# Kube_LoRaWAN_Module.net
KiCad netlist of a schematic drawn in EAGLE
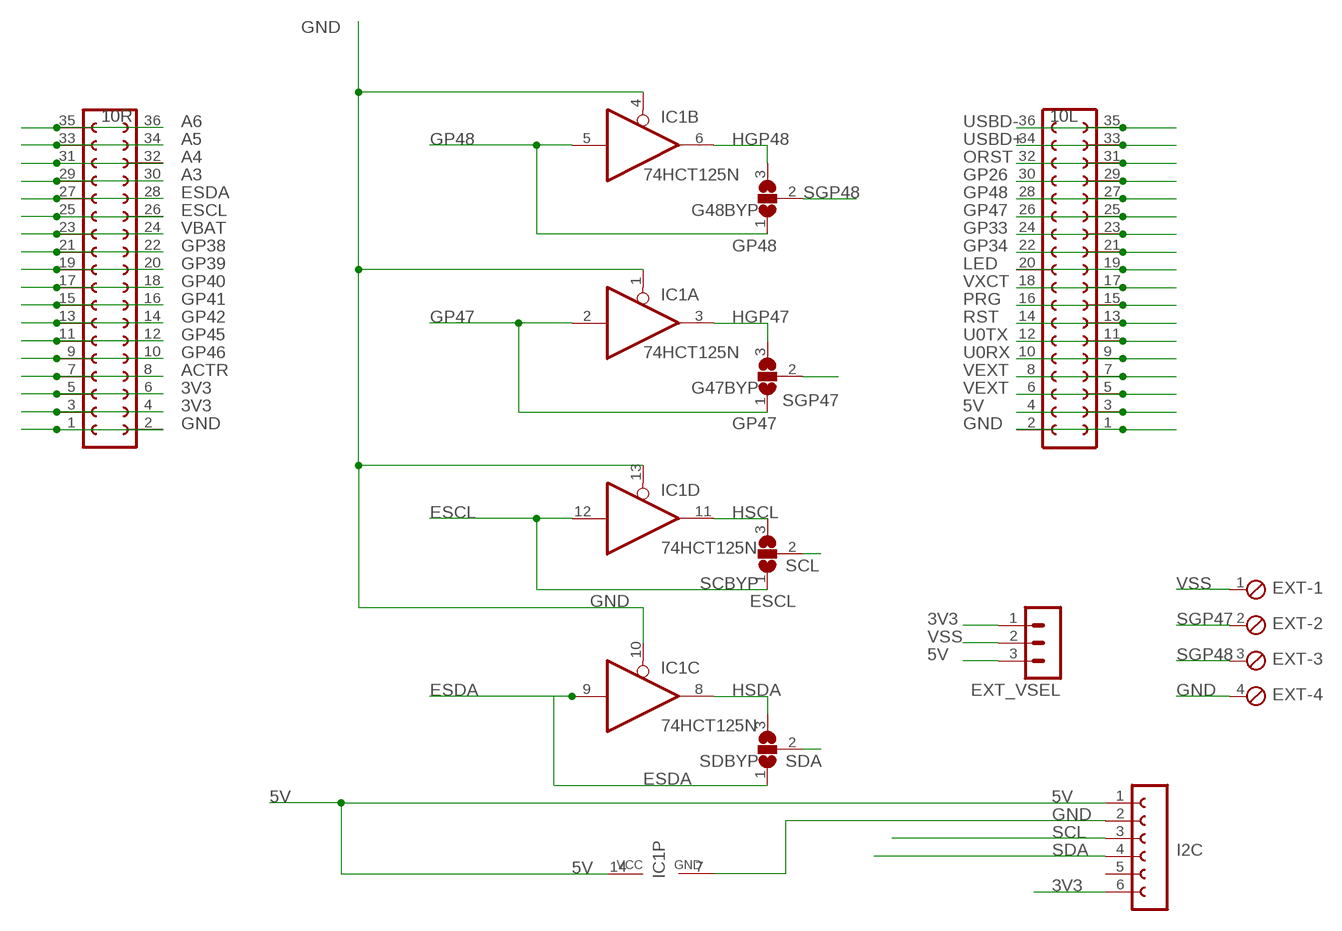
[diagram p0: schematic, sheet 1]

(export (version "E")
  (design (tool "Eeschema 10.0.6"))
  (components
    (comp (ref "10L")
      (value "15")
      (footprint "eagle-import:FE18-2")
      (libsource (lib "eagle-import") (part "FE18-2"))
    )
    (comp (ref "10R")
      (value "15")
      (footprint "eagle-import:FE18-2")
      (libsource (lib "eagle-import") (part "FE18-2"))
    )
    (comp (ref "EXT")
      (value "MPT4")
      (footprint "eagle-import:4POL254")
      (libsource (lib "eagle-import") (part "MPT4"))
    )
    (comp (ref "EXT_VSEL")
      (value "MA03-1")
      (footprint "eagle-import:MA03-1")
      (libsource (lib "eagle-import") (part "MA03-1"))
    )
    (comp (ref "G47BYP")
      (value "SJ2W")
      (footprint "eagle-import:SJ_2")
      (libsource (lib "eagle-import") (part "SJ2W"))
    )
    (comp (ref "G48BYP")
      (value "SJ2W")
      (footprint "eagle-import:SJ_2")
      (libsource (lib "eagle-import") (part "SJ2W"))
    )
    (comp (ref "I2C")
      (value "FE06-1")
      (footprint "eagle-import:FE06")
      (libsource (lib "eagle-import") (part "FE06-1"))
    )
    (comp (ref "IC1")
      (value "74HCT125N")
      (footprint "eagle-import:DIL14")
      (libsource (lib "eagle-import") (part "74125NHCT"))
    )
    (comp (ref "SCBYP")
      (value "SJ2W")
      (footprint "eagle-import:SJ_2")
      (libsource (lib "eagle-import") (part "SJ2W"))
    )
    (comp (ref "SDBYP")
      (value "SJ2W")
      (footprint "eagle-import:SJ_2")
      (libsource (lib "eagle-import") (part "SJ2W"))
    )
  )
  (nets
    (net (code "1") (name "/3V3") (class "Default")
      (node (ref "10R") (pin "3") (pinfunction "3_3") (pintype "passive"))
      (node (ref "10R") (pin "4") (pinfunction "4_4") (pintype "passive"))
      (node (ref "10R") (pin "5") (pinfunction "5_5") (pintype "passive"))
      (node (ref "10R") (pin "6") (pinfunction "6_6") (pintype "passive"))
      (node (ref "EXT_VSEL") (pin "1") (pinfunction "1_1") (pintype "passive"))
      (node (ref "I2C") (pin "6") (pinfunction "6_6") (pintype "passive"))
    )
    (net (code "2") (name "/5V") (class "Default")
      (node (ref "10L") (pin "3") (pinfunction "3_3") (pintype "passive"))
      (node (ref "10L") (pin "4") (pinfunction "4_4") (pintype "passive"))
      (node (ref "EXT_VSEL") (pin "3") (pinfunction "3_3") (pintype "passive"))
      (node (ref "I2C") (pin "1") (pinfunction "1_1") (pintype "passive"))
      (node (ref "IC1") (pin "14") (pinfunction "VCC_14") (pintype "power_in"))
    )
    (net (code "3") (name "/A3") (class "Default")
      (node (ref "10R") (pin "29") (pinfunction "29_29") (pintype "passive"))
      (node (ref "10R") (pin "30") (pinfunction "30_30") (pintype "passive"))
    )
    (net (code "4") (name "/A4") (class "Default")
      (node (ref "10R") (pin "31") (pinfunction "31_31") (pintype "passive"))
      (node (ref "10R") (pin "32") (pinfunction "32_32") (pintype "passive"))
    )
    (net (code "5") (name "/A5") (class "Default")
      (node (ref "10R") (pin "33") (pinfunction "33_33") (pintype "passive"))
      (node (ref "10R") (pin "34") (pinfunction "34_34") (pintype "passive"))
    )
    (net (code "6") (name "/A6") (class "Default")
      (node (ref "10R") (pin "35") (pinfunction "35_35") (pintype "passive"))
      (node (ref "10R") (pin "36") (pinfunction "36_36") (pintype "passive"))
    )
    (net (code "7") (name "/ACTR") (class "Default")
      (node (ref "10R") (pin "7") (pinfunction "7_7") (pintype "passive"))
      (node (ref "10R") (pin "8") (pinfunction "8_8") (pintype "passive"))
    )
    (net (code "8") (name "/ESCL") (class "Default")
      (node (ref "10R") (pin "25") (pinfunction "25_25") (pintype "passive"))
      (node (ref "10R") (pin "26") (pinfunction "26_26") (pintype "passive"))
      (node (ref "IC1") (pin "12") (pinfunction "I_12") (pintype "input"))
      (node (ref "SCBYP") (pin "1") (pinfunction "1_1") (pintype "passive"))
    )
    (net (code "9") (name "/ESDA") (class "Default")
      (node (ref "10R") (pin "27") (pinfunction "27_27") (pintype "passive"))
      (node (ref "10R") (pin "28") (pinfunction "28_28") (pintype "passive"))
      (node (ref "IC1") (pin "9") (pinfunction "I_9") (pintype "input"))
      (node (ref "SDBYP") (pin "1") (pinfunction "1_1") (pintype "passive"))
    )
    (net (code "10") (name "/GND") (class "Default")
      (node (ref "10L") (pin "1") (pinfunction "1_1") (pintype "passive"))
      (node (ref "10L") (pin "2") (pinfunction "2_2") (pintype "passive"))
      (node (ref "10R") (pin "1") (pinfunction "1_1") (pintype "passive"))
      (node (ref "10R") (pin "2") (pinfunction "2_2") (pintype "passive"))
      (node (ref "EXT") (pin "4") (pinfunction "1_4") (pintype "passive"))
      (node (ref "I2C") (pin "2") (pinfunction "2_2") (pintype "passive"))
      (node (ref "IC1") (pin "1") (pinfunction "OE_1") (pintype "input"))
      (node (ref "IC1") (pin "10") (pinfunction "OE_10") (pintype "input"))
      (node (ref "IC1") (pin "13") (pinfunction "OE_13") (pintype "input"))
      (node (ref "IC1") (pin "4") (pinfunction "OE_4") (pintype "input"))
      (node (ref "IC1") (pin "7") (pinfunction "GND_7") (pintype "power_in"))
    )
    (net (code "11") (name "/GP26") (class "Default")
      (node (ref "10L") (pin "29") (pinfunction "29_29") (pintype "passive"))
      (node (ref "10L") (pin "30") (pinfunction "30_30") (pintype "passive"))
    )
    (net (code "12") (name "/GP33") (class "Default")
      (node (ref "10L") (pin "23") (pinfunction "23_23") (pintype "passive"))
      (node (ref "10L") (pin "24") (pinfunction "24_24") (pintype "passive"))
    )
    (net (code "13") (name "/GP34") (class "Default")
      (node (ref "10L") (pin "21") (pinfunction "21_21") (pintype "passive"))
      (node (ref "10L") (pin "22") (pinfunction "22_22") (pintype "passive"))
    )
    (net (code "14") (name "/GP38") (class "Default")
      (node (ref "10R") (pin "21") (pinfunction "21_21") (pintype "passive"))
      (node (ref "10R") (pin "22") (pinfunction "22_22") (pintype "passive"))
    )
    (net (code "15") (name "/GP39") (class "Default")
      (node (ref "10R") (pin "19") (pinfunction "19_19") (pintype "passive"))
      (node (ref "10R") (pin "20") (pinfunction "20_20") (pintype "passive"))
    )
    (net (code "16") (name "/GP40") (class "Default")
      (node (ref "10R") (pin "17") (pinfunction "17_17") (pintype "passive"))
      (node (ref "10R") (pin "18") (pinfunction "18_18") (pintype "passive"))
    )
    (net (code "17") (name "/GP41") (class "Default")
      (node (ref "10R") (pin "15") (pinfunction "15_15") (pintype "passive"))
      (node (ref "10R") (pin "16") (pinfunction "16_16") (pintype "passive"))
    )
    (net (code "18") (name "/GP42") (class "Default")
      (node (ref "10R") (pin "13") (pinfunction "13_13") (pintype "passive"))
      (node (ref "10R") (pin "14") (pinfunction "14_14") (pintype "passive"))
    )
    (net (code "19") (name "/GP45") (class "Default")
      (node (ref "10R") (pin "11") (pinfunction "11_11") (pintype "passive"))
      (node (ref "10R") (pin "12") (pinfunction "12_12") (pintype "passive"))
    )
    (net (code "20") (name "/GP46") (class "Default")
      (node (ref "10R") (pin "10") (pinfunction "10_10") (pintype "passive"))
      (node (ref "10R") (pin "9") (pinfunction "9_9") (pintype "passive"))
    )
    (net (code "21") (name "/GP47") (class "Default")
      (node (ref "10L") (pin "25") (pinfunction "25_25") (pintype "passive"))
      (node (ref "10L") (pin "26") (pinfunction "26_26") (pintype "passive"))
      (node (ref "G47BYP") (pin "1") (pinfunction "1_1") (pintype "passive"))
      (node (ref "IC1") (pin "2") (pinfunction "I_2") (pintype "input"))
    )
    (net (code "22") (name "/GP48") (class "Default")
      (node (ref "10L") (pin "27") (pinfunction "27_27") (pintype "passive"))
      (node (ref "10L") (pin "28") (pinfunction "28_28") (pintype "passive"))
      (node (ref "G48BYP") (pin "1") (pinfunction "1_1") (pintype "passive"))
      (node (ref "IC1") (pin "5") (pinfunction "I_5") (pintype "input"))
    )
    (net (code "23") (name "/HGP47") (class "Default")
      (node (ref "G47BYP") (pin "3") (pinfunction "3_3") (pintype "passive"))
      (node (ref "IC1") (pin "3") (pinfunction "O_3") (pintype "tri_state"))
    )
    (net (code "24") (name "/HGP48") (class "Default")
      (node (ref "G48BYP") (pin "3") (pinfunction "3_3") (pintype "passive"))
      (node (ref "IC1") (pin "6") (pinfunction "O_6") (pintype "tri_state"))
    )
    (net (code "25") (name "/HSCL") (class "Default")
      (node (ref "IC1") (pin "11") (pinfunction "O_11") (pintype "tri_state"))
      (node (ref "SCBYP") (pin "3") (pinfunction "3_3") (pintype "passive"))
    )
    (net (code "26") (name "/HSDA") (class "Default")
      (node (ref "IC1") (pin "8") (pinfunction "O_8") (pintype "tri_state"))
      (node (ref "SDBYP") (pin "3") (pinfunction "3_3") (pintype "passive"))
    )
    (net (code "27") (name "/LED") (class "Default")
      (node (ref "10L") (pin "19") (pinfunction "19_19") (pintype "passive"))
      (node (ref "10L") (pin "20") (pinfunction "20_20") (pintype "passive"))
    )
    (net (code "28") (name "/ORST") (class "Default")
      (node (ref "10L") (pin "31") (pinfunction "31_31") (pintype "passive"))
      (node (ref "10L") (pin "32") (pinfunction "32_32") (pintype "passive"))
    )
    (net (code "29") (name "/PRG") (class "Default")
      (node (ref "10L") (pin "15") (pinfunction "15_15") (pintype "passive"))
      (node (ref "10L") (pin "16") (pinfunction "16_16") (pintype "passive"))
    )
    (net (code "30") (name "/RST") (class "Default")
      (node (ref "10L") (pin "13") (pinfunction "13_13") (pintype "passive"))
      (node (ref "10L") (pin "14") (pinfunction "14_14") (pintype "passive"))
    )
    (net (code "31") (name "/SCL") (class "Default")
      (node (ref "I2C") (pin "3") (pinfunction "3_3") (pintype "passive"))
      (node (ref "SCBYP") (pin "2") (pinfunction "2_2") (pintype "passive"))
    )
    (net (code "32") (name "/SDA") (class "Default")
      (node (ref "I2C") (pin "4") (pinfunction "4_4") (pintype "passive"))
      (node (ref "SDBYP") (pin "2") (pinfunction "2_2") (pintype "passive"))
    )
    (net (code "33") (name "/SGP47") (class "Default")
      (node (ref "EXT") (pin "2") (pinfunction "1_2") (pintype "passive"))
      (node (ref "G47BYP") (pin "2") (pinfunction "2_2") (pintype "passive"))
    )
    (net (code "34") (name "/SGP48") (class "Default")
      (node (ref "EXT") (pin "3") (pinfunction "1_3") (pintype "passive"))
      (node (ref "G48BYP") (pin "2") (pinfunction "2_2") (pintype "passive"))
    )
    (net (code "35") (name "/U0RX") (class "Default")
      (node (ref "10L") (pin "10") (pinfunction "10_10") (pintype "passive"))
      (node (ref "10L") (pin "9") (pinfunction "9_9") (pintype "passive"))
    )
    (net (code "36") (name "/U0TX") (class "Default")
      (node (ref "10L") (pin "11") (pinfunction "11_11") (pintype "passive"))
      (node (ref "10L") (pin "12") (pinfunction "12_12") (pintype "passive"))
    )
    (net (code "37") (name "/USBD+") (class "Default")
      (node (ref "10L") (pin "33") (pinfunction "33_33") (pintype "passive"))
      (node (ref "10L") (pin "34") (pinfunction "34_34") (pintype "passive"))
    )
    (net (code "38") (name "/USBD-") (class "Default")
      (node (ref "10L") (pin "35") (pinfunction "35_35") (pintype "passive"))
      (node (ref "10L") (pin "36") (pinfunction "36_36") (pintype "passive"))
    )
    (net (code "39") (name "/VBAT") (class "Default")
      (node (ref "10R") (pin "23") (pinfunction "23_23") (pintype "passive"))
      (node (ref "10R") (pin "24") (pinfunction "24_24") (pintype "passive"))
    )
    (net (code "40") (name "/VEXT") (class "Default")
      (node (ref "10L") (pin "5") (pinfunction "5_5") (pintype "passive"))
      (node (ref "10L") (pin "6") (pinfunction "6_6") (pintype "passive"))
      (node (ref "10L") (pin "7") (pinfunction "7_7") (pintype "passive"))
      (node (ref "10L") (pin "8") (pinfunction "8_8") (pintype "passive"))
    )
    (net (code "41") (name "/VSS") (class "Default")
      (node (ref "EXT") (pin "1") (pinfunction "1_1") (pintype "passive"))
      (node (ref "EXT_VSEL") (pin "2") (pinfunction "2_2") (pintype "passive"))
    )
    (net (code "42") (name "/VXCT") (class "Default")
      (node (ref "10L") (pin "17") (pinfunction "17_17") (pintype "passive"))
      (node (ref "10L") (pin "18") (pinfunction "18_18") (pintype "passive"))
    )
    (net (code "43") (name "unconnected-(I2C-Pad5)") (class "Default")
      (node (ref "I2C") (pin "5") (pinfunction "5_5") (pintype "passive"))
    )
  )
)
